# ATTiny1614_Mainboard.net
KiCad netlist of a schematic drawn in EAGLE
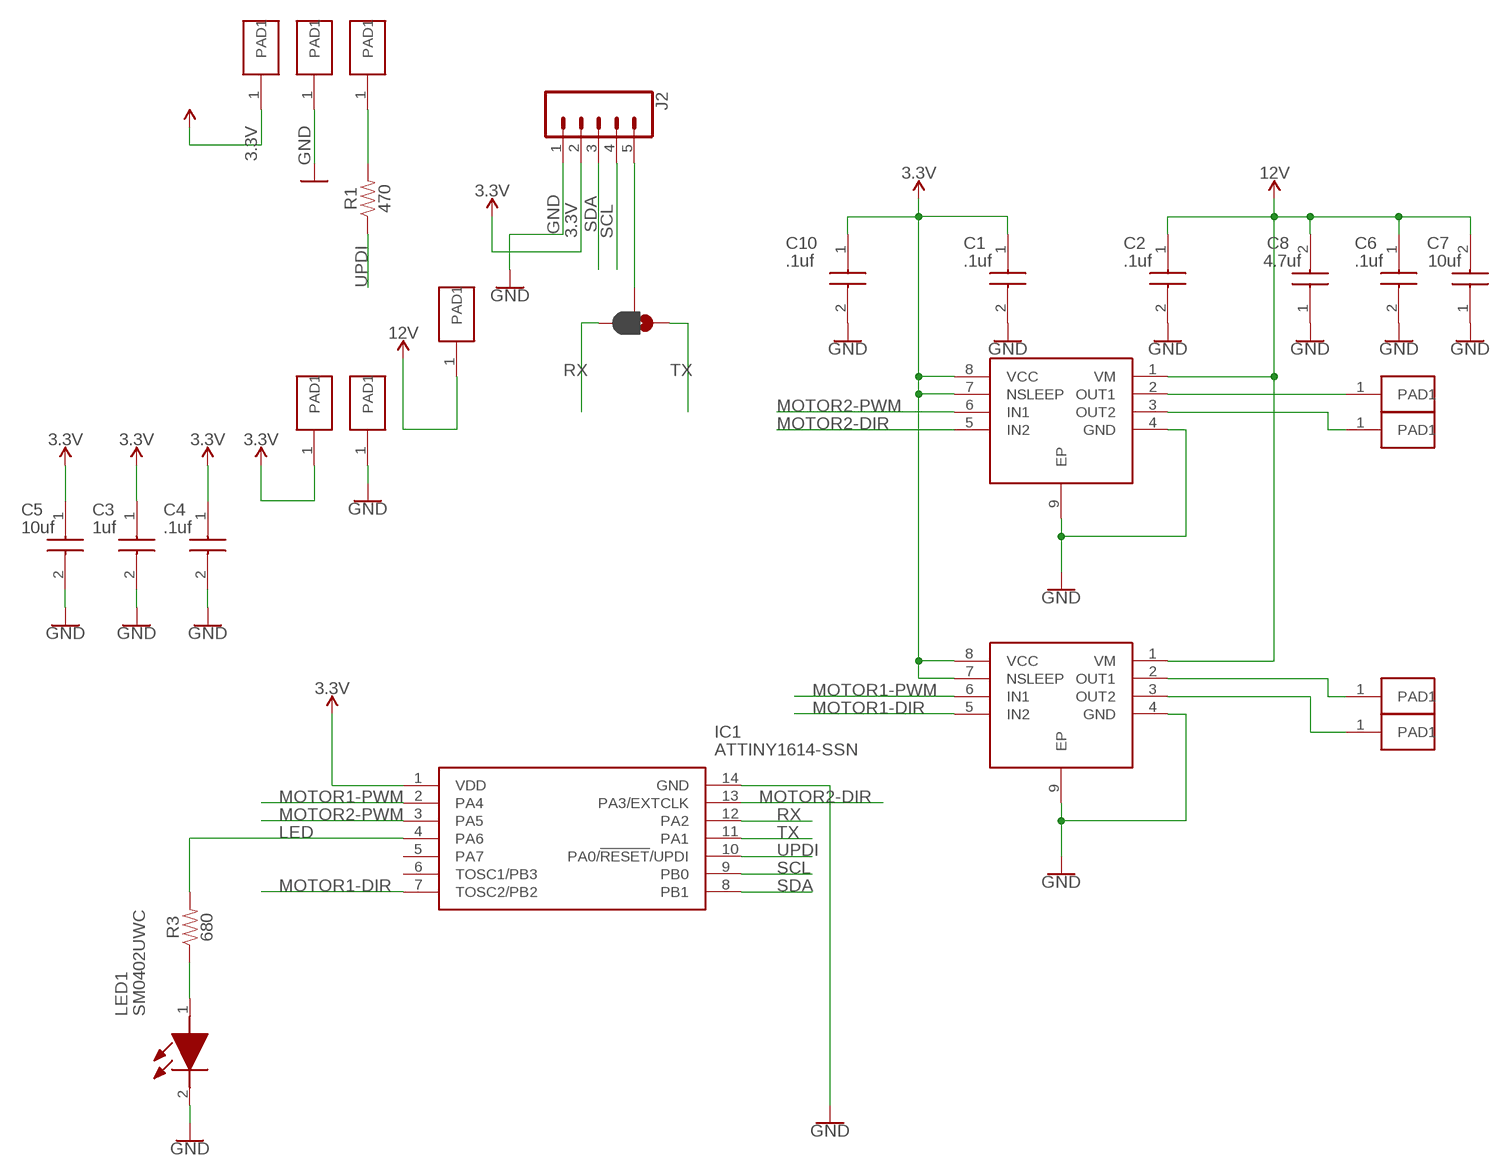
[diagram p0: schematic, sheet 1]

(export (version "E")
  (design (tool "Eeschema 10.0.6"))
  (components
    (comp (ref "C1")
      (value ".1uf")
      (footprint "eagle-import:CAPC1005X56N")
      (fields
        (field (name "MANUFACTURER_PART_NUMBER") "04026C105KAT2A")
        (field (name "MOUSER_PART_NUMBER") "581-04026C105KAT2A")
      )
      (libsource (lib "eagle-import") (part "0402-CAPCAPACITOR-0402"))
    )
    (comp (ref "C2")
      (value ".1uf")
      (footprint "eagle-import:CAPC1005X56N")
      (fields
        (field (name "MANUFACTURER_PART_NUMBER") "04026C105KAT2A")
        (field (name "MOUSER_PART_NUMBER") "581-04026C105KAT2A")
      )
      (libsource (lib "eagle-import") (part "0402-CAPCAPACITOR-0402"))
    )
    (comp (ref "C3")
      (value "1uf")
      (footprint "eagle-import:CAPC1005X56N")
      (fields
        (field (name "MANUFACTURER_PART_NUMBER") "04026C105KAT2A")
        (field (name "MOUSER_PART_NUMBER") "581-04026C105KAT2A")
      )
      (libsource (lib "eagle-import") (part "0402-CAPCAPACITOR-0402"))
    )
    (comp (ref "C4")
      (value ".1uf")
      (footprint "eagle-import:CAPC1005X56N")
      (fields
        (field (name "MANUFACTURER_PART_NUMBER") "04026C105KAT2A")
        (field (name "MOUSER_PART_NUMBER") "581-04026C105KAT2A")
      )
      (libsource (lib "eagle-import") (part "0402-CAPCAPACITOR-0402"))
    )
    (comp (ref "C5")
      (value "10uf")
      (footprint "eagle-import:CAPC1005X56N")
      (fields
        (field (name "MANUFACTURER_PART_NUMBER") "04026C105KAT2A")
        (field (name "MOUSER_PART_NUMBER") "581-04026C105KAT2A")
      )
      (libsource (lib "eagle-import") (part "0402-CAPCAPACITOR-0402"))
    )
    (comp (ref "C6")
      (value ".1uf")
      (footprint "eagle-import:CAPC1005X56N")
      (fields
        (field (name "MANUFACTURER_PART_NUMBER") "04026C105KAT2A")
        (field (name "MOUSER_PART_NUMBER") "581-04026C105KAT2A")
      )
      (libsource (lib "eagle-import") (part "0402-CAPCAPACITOR-0402"))
    )
    (comp (ref "C7")
      (value "10uf")
      (footprint "eagle-import:CAPC1005X56N")
      (fields
        (field (name "MANUFACTURER_PART_NUMBER") "04026C105KAT2A")
        (field (name "MOUSER_PART_NUMBER") "581-04026C105KAT2A")
      )
      (libsource (lib "eagle-import") (part "0402-CAPCAPACITOR-0402"))
    )
    (comp (ref "C8")
      (value "4.7uf")
      (footprint "eagle-import:CAPC1005X56N")
      (fields
        (field (name "MANUFACTURER_PART_NUMBER") "04026C105KAT2A")
        (field (name "MOUSER_PART_NUMBER") "581-04026C105KAT2A")
      )
      (libsource (lib "eagle-import") (part "0402-CAPCAPACITOR-0402"))
    )
    (comp (ref "C10")
      (value ".1uf")
      (footprint "eagle-import:CAPC1005X56N")
      (fields
        (field (name "MANUFACTURER_PART_NUMBER") "04026C105KAT2A")
        (field (name "MOUSER_PART_NUMBER") "581-04026C105KAT2A")
      )
      (libsource (lib "eagle-import") (part "0402-CAPCAPACITOR-0402"))
    )
    (comp (ref "IC1")
      (value "ATTINY1614-SSN")
      (footprint "eagle-import:SOIC127P600X175-14N")
      (fields (field (name "MOUSER_PART_NUMBER") "556-ATTINY1614-SSN"))
      (libsource (lib "eagle-import") (part "ATTINY1614-SSN"))
    )
    (comp (ref "IC2")
      (value "DRV8837DSGR")
      (footprint "eagle-import:SON50P200X200X80-9N")
      (fields (field (name "MOUSER_PART_NUMBER") "595-DRV8837DSGR"))
      (libsource (lib "eagle-import") (part "DRV8837DSGR"))
    )
    (comp (ref "IC3")
      (value "DRV8837DSGR")
      (footprint "eagle-import:SON50P200X200X80-9N")
      (fields (field (name "MOUSER_PART_NUMBER") "595-DRV8837DSGR"))
      (libsource (lib "eagle-import") (part "DRV8837DSGR"))
    )
    (comp (ref "J2")
      (value "CONN_051.27MM")
      (footprint "eagle-import:1X05_1.27MM")
      (libsource (lib "eagle-import") (part "CONN_051.27MM"))
    )
    (comp (ref "JP1")
      (value "JUMPER-SMT_3_1-NC_PASTE_NO-SILK")
      (footprint "eagle-import:SMT-JUMPER_3_1-NC_PASTE_NO-SILK")
      (libsource (lib "eagle-import") (part "JUMPER-SMT_3_1-NC_PASTE_NO-SILK"))
    )
    (comp (ref "LED1")
      (value "SM0402UWC")
      (footprint "eagle-import:SM0402UWC")
      (fields (field (name "MOUSER_PART_NUMBER") "749-SM0402UWC"))
      (libsource (lib "eagle-import") (part "SM0402UWC"))
    )
    (comp (ref "R1")
      (value "470")
      (footprint "eagle-import:0402")
      (libsource (lib "eagle-import") (part "470OHM-0402-1/16W-5%"))
    )
    (comp (ref "R3")
      (value "680")
      (footprint "eagle-import:0402")
      (libsource (lib "eagle-import") (part "470OHM-0402-1/16W-5%"))
    )
    (comp (ref "U$1")
      (value "SINGLE_1.27MM_HOLE")
      (footprint "eagle-import:1.27MM_SINGLE_HOLE")
      (libsource (lib "eagle-import") (part "SINGLE_1.27MM_HOLE"))
    )
    (comp (ref "U$2")
      (value "SINGLE_1.27MM_HOLE")
      (footprint "eagle-import:1.27MM_SINGLE_HOLE")
      (libsource (lib "eagle-import") (part "SINGLE_1.27MM_HOLE"))
    )
    (comp (ref "U$3")
      (value "SINGLE_1.27MM_HOLE")
      (footprint "eagle-import:1.27MM_SINGLE_HOLE")
      (libsource (lib "eagle-import") (part "SINGLE_1.27MM_HOLE"))
    )
    (comp (ref "U$4")
      (value "SINGLE_1.27MM_HOLE")
      (footprint "eagle-import:1.27MM_SINGLE_HOLE")
      (libsource (lib "eagle-import") (part "SINGLE_1.27MM_HOLE"))
    )
    (comp (ref "U$5")
      (value "SINGLE_1.27MM_HOLE")
      (footprint "eagle-import:1.27MM_SINGLE_HOLE")
      (libsource (lib "eagle-import") (part "SINGLE_1.27MM_HOLE"))
    )
    (comp (ref "U$6")
      (value "SINGLE_1.27MM_HOLE")
      (footprint "eagle-import:1.27MM_SINGLE_HOLE")
      (libsource (lib "eagle-import") (part "SINGLE_1.27MM_HOLE"))
    )
    (comp (ref "U$7")
      (value "SINGLE_1.27MM_HOLE")
      (footprint "eagle-import:1.27MM_SINGLE_HOLE")
      (libsource (lib "eagle-import") (part "SINGLE_1.27MM_HOLE"))
    )
    (comp (ref "U$8")
      (value "SINGLE_1.27MM_HOLE")
      (footprint "eagle-import:1.27MM_SINGLE_HOLE")
      (libsource (lib "eagle-import") (part "SINGLE_1.27MM_HOLE"))
    )
    (comp (ref "U$9")
      (value "SINGLE_1.27MM_HOLE")
      (footprint "eagle-import:1.27MM_SINGLE_HOLE")
      (libsource (lib "eagle-import") (part "SINGLE_1.27MM_HOLE"))
    )
    (comp (ref "U$12")
      (value "SINGLE_1.27MM_HOLE")
      (footprint "eagle-import:1.27MM_SINGLE_HOLE")
      (libsource (lib "eagle-import") (part "SINGLE_1.27MM_HOLE"))
    )
  )
  (nets
    (net (code "1") (name "/LED") (class "Default")
      (node (ref "IC1") (pin "4") (pinfunction "PA6_4") (pintype "bidirectional"))
      (node (ref "R3") (pin "2") (pinfunction "2_2") (pintype "passive"))
    )
    (net (code "2") (name "/MOTOR1-DIR") (class "Default")
      (node (ref "IC1") (pin "7") (pinfunction "TOSC2/PB2_7") (pintype "bidirectional"))
      (node (ref "IC2") (pin "5") (pinfunction "IN2_5") (pintype "bidirectional"))
    )
    (net (code "3") (name "/MOTOR1-PWM") (class "Default")
      (node (ref "IC1") (pin "2") (pinfunction "PA4_2") (pintype "bidirectional"))
      (node (ref "IC2") (pin "6") (pinfunction "IN1_6") (pintype "bidirectional"))
    )
    (net (code "4") (name "/MOTOR2-DIR") (class "Default")
      (node (ref "IC1") (pin "13") (pinfunction "PA3/EXTCLK_13") (pintype "bidirectional"))
      (node (ref "IC3") (pin "5") (pinfunction "IN2_5") (pintype "bidirectional"))
    )
    (net (code "5") (name "/MOTOR2-PWM") (class "Default")
      (node (ref "IC1") (pin "3") (pinfunction "PA5_3") (pintype "bidirectional"))
      (node (ref "IC3") (pin "6") (pinfunction "IN1_6") (pintype "bidirectional"))
    )
    (net (code "6") (name "/RX") (class "Default")
      (node (ref "IC1") (pin "12") (pinfunction "PA2_12") (pintype "bidirectional"))
      (node (ref "JP1") (pin "3") (pinfunction "3_3") (pintype "passive"))
    )
    (net (code "7") (name "/SCL") (class "Default")
      (node (ref "IC1") (pin "9") (pinfunction "PB0_9") (pintype "bidirectional"))
      (node (ref "J2") (pin "4") (pinfunction "4_4") (pintype "passive"))
    )
    (net (code "8") (name "/SDA") (class "Default")
      (node (ref "IC1") (pin "8") (pinfunction "PB1_8") (pintype "bidirectional"))
      (node (ref "J2") (pin "3") (pinfunction "3_3") (pintype "passive"))
    )
    (net (code "9") (name "/TX") (class "Default")
      (node (ref "IC1") (pin "11") (pinfunction "PA1_11") (pintype "bidirectional"))
      (node (ref "JP1") (pin "1") (pinfunction "1_1") (pintype "passive"))
    )
    (net (code "10") (name "/UPDI") (class "Default")
      (node (ref "IC1") (pin "10") (pinfunction "PA0/~{RESET}/UPDI_10") (pintype "bidirectional"))
      (node (ref "R1") (pin "1") (pinfunction "1_1") (pintype "passive"))
    )
    (net (code "11") (name "3.3V") (class "Default")
      (node (ref "C1") (pin "1") (pinfunction "1_1") (pintype "bidirectional"))
      (node (ref "C10") (pin "1") (pinfunction "1_1") (pintype "bidirectional"))
      (node (ref "C3") (pin "1") (pinfunction "1_1") (pintype "bidirectional"))
      (node (ref "C4") (pin "1") (pinfunction "1_1") (pintype "bidirectional"))
      (node (ref "C5") (pin "1") (pinfunction "1_1") (pintype "bidirectional"))
      (node (ref "IC1") (pin "1") (pinfunction "VDD_1") (pintype "bidirectional"))
      (node (ref "IC2") (pin "7") (pinfunction "NSLEEP_7") (pintype "bidirectional"))
      (node (ref "IC2") (pin "8") (pinfunction "VCC_8") (pintype "bidirectional"))
      (node (ref "IC3") (pin "7") (pinfunction "NSLEEP_7") (pintype "bidirectional"))
      (node (ref "IC3") (pin "8") (pinfunction "VCC_8") (pintype "bidirectional"))
      (node (ref "J2") (pin "2") (pinfunction "2_2") (pintype "passive"))
      (node (ref "U$1") (pin "1") (pinfunction "PAD1_1") (pintype "bidirectional"))
      (node (ref "U$4") (pin "1") (pinfunction "PAD1_1") (pintype "bidirectional"))
    )
    (net (code "12") (name "12V") (class "Default")
      (node (ref "C2") (pin "1") (pinfunction "1_1") (pintype "bidirectional"))
      (node (ref "C6") (pin "1") (pinfunction "1_1") (pintype "bidirectional"))
      (node (ref "C7") (pin "2") (pinfunction "2_2") (pintype "bidirectional"))
      (node (ref "C8") (pin "2") (pinfunction "2_2") (pintype "bidirectional"))
      (node (ref "IC2") (pin "1") (pinfunction "VM_1") (pintype "bidirectional"))
      (node (ref "IC3") (pin "1") (pinfunction "VM_1") (pintype "bidirectional"))
      (node (ref "U$12") (pin "1") (pinfunction "PAD1_1") (pintype "bidirectional"))
    )
    (net (code "13") (name "GND") (class "Default")
      (node (ref "C1") (pin "2") (pinfunction "2_2") (pintype "bidirectional"))
      (node (ref "C10") (pin "2") (pinfunction "2_2") (pintype "bidirectional"))
      (node (ref "C2") (pin "2") (pinfunction "2_2") (pintype "bidirectional"))
      (node (ref "C3") (pin "2") (pinfunction "2_2") (pintype "bidirectional"))
      (node (ref "C4") (pin "2") (pinfunction "2_2") (pintype "bidirectional"))
      (node (ref "C5") (pin "2") (pinfunction "2_2") (pintype "bidirectional"))
      (node (ref "C6") (pin "2") (pinfunction "2_2") (pintype "bidirectional"))
      (node (ref "C7") (pin "1") (pinfunction "1_1") (pintype "bidirectional"))
      (node (ref "C8") (pin "1") (pinfunction "1_1") (pintype "bidirectional"))
      (node (ref "IC1") (pin "14") (pinfunction "GND_14") (pintype "bidirectional"))
      (node (ref "IC2") (pin "4") (pinfunction "GND_4") (pintype "bidirectional"))
      (node (ref "IC2") (pin "9") (pinfunction "EP_9") (pintype "bidirectional"))
      (node (ref "IC3") (pin "4") (pinfunction "GND_4") (pintype "bidirectional"))
      (node (ref "IC3") (pin "9") (pinfunction "EP_9") (pintype "bidirectional"))
      (node (ref "J2") (pin "1") (pinfunction "1_1") (pintype "passive"))
      (node (ref "LED1") (pin "2") (pinfunction "K_2") (pintype "bidirectional"))
      (node (ref "U$2") (pin "1") (pinfunction "PAD1_1") (pintype "bidirectional"))
      (node (ref "U$3") (pin "1") (pinfunction "PAD1_1") (pintype "bidirectional"))
    )
    (net (code "14") (name "Net-(IC2-OUT1)") (class "Default")
      (node (ref "IC2") (pin "2") (pinfunction "OUT1_2") (pintype "bidirectional"))
      (node (ref "U$8") (pin "1") (pinfunction "PAD1_1") (pintype "bidirectional"))
    )
    (net (code "15") (name "Net-(IC2-OUT2)") (class "Default")
      (node (ref "IC2") (pin "3") (pinfunction "OUT2_3") (pintype "bidirectional"))
      (node (ref "U$9") (pin "1") (pinfunction "PAD1_1") (pintype "bidirectional"))
    )
    (net (code "16") (name "Net-(IC3-OUT1)") (class "Default")
      (node (ref "IC3") (pin "2") (pinfunction "OUT1_2") (pintype "bidirectional"))
      (node (ref "U$6") (pin "1") (pinfunction "PAD1_1") (pintype "bidirectional"))
    )
    (net (code "17") (name "Net-(IC3-OUT2)") (class "Default")
      (node (ref "IC3") (pin "3") (pinfunction "OUT2_3") (pintype "bidirectional"))
      (node (ref "U$7") (pin "1") (pinfunction "PAD1_1") (pintype "bidirectional"))
    )
    (net (code "18") (name "Net-(J2-Pad5)") (class "Default")
      (node (ref "J2") (pin "5") (pinfunction "5_5") (pintype "passive"))
      (node (ref "JP1") (pin "2") (pinfunction "2_2") (pintype "passive"))
    )
    (net (code "19") (name "Net-(LED1-A)") (class "Default")
      (node (ref "LED1") (pin "1") (pinfunction "A_1") (pintype "bidirectional"))
      (node (ref "R3") (pin "1") (pinfunction "1_1") (pintype "passive"))
    )
    (net (code "20") (name "Net-(U$5-PAD1)") (class "Default")
      (node (ref "R1") (pin "2") (pinfunction "2_2") (pintype "passive"))
      (node (ref "U$5") (pin "1") (pinfunction "PAD1_1") (pintype "bidirectional"))
    )
    (net (code "21") (name "unconnected-(IC1-PA7-Pad5)") (class "Default")
      (node (ref "IC1") (pin "5") (pinfunction "PA7_5") (pintype "bidirectional"))
    )
    (net (code "22") (name "unconnected-(IC1-TOSC1{slash}PB3-Pad6)") (class "Default")
      (node (ref "IC1") (pin "6") (pinfunction "TOSC1/PB3_6") (pintype "bidirectional"))
    )
  )
)
